# SCH-Unified_Sheet_2_Altium.net
KiCad netlist of a schematic drawn in Altium Designer
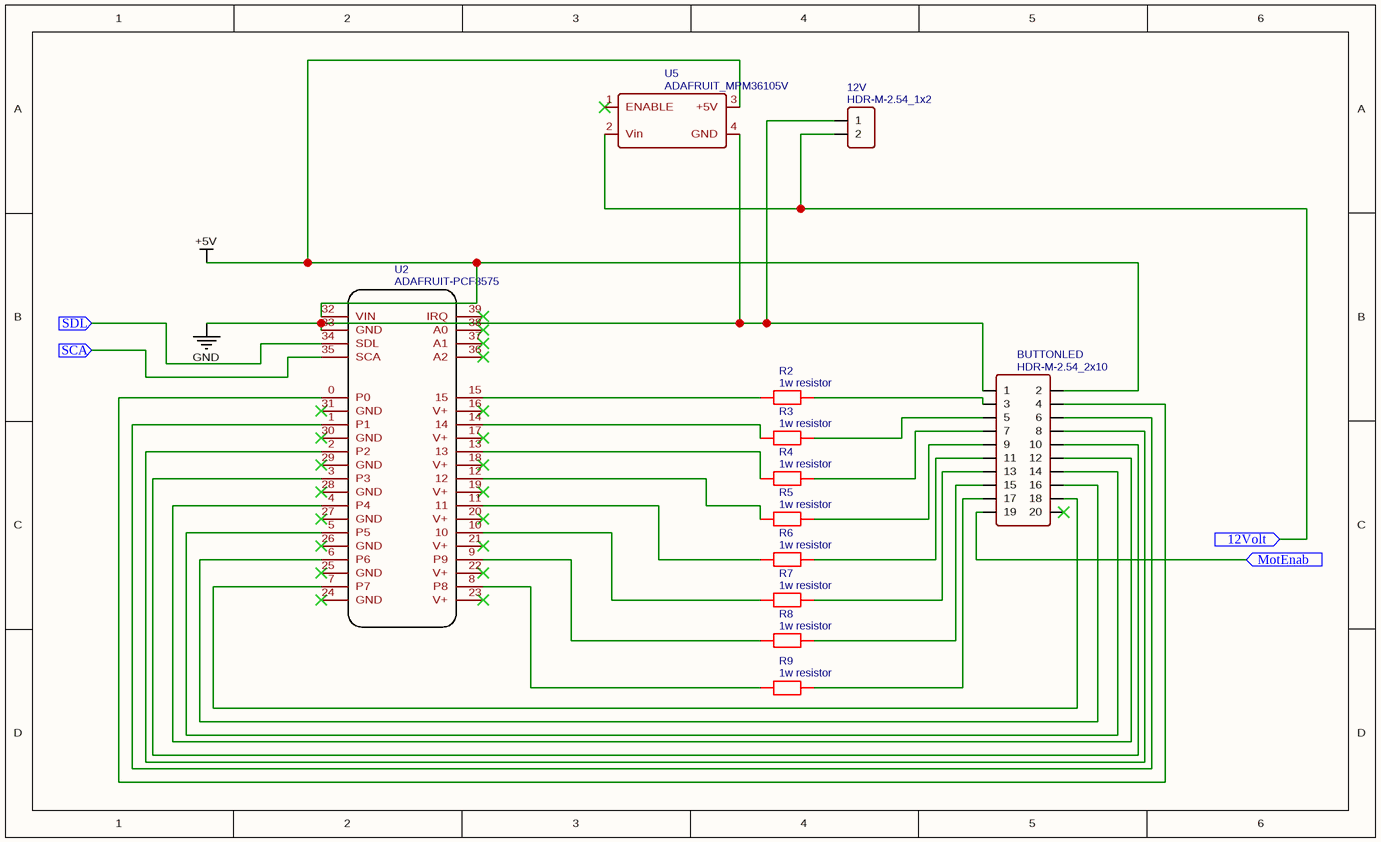
[diagram p0: SCH-Unified_Sheet_2_Altium.schdoc]

(export (version "E")
  (design (tool "Eeschema 10.0.6"))
  (components
    (comp (ref "12V")
      (value "HDR-M-2.54_1x2")
      (fields (field (name "CONTRIBUTOR") "LCEDA_Lib"))
      (libsource (lib "altium-import") (part "root_0_HDR-M-2.54_1x2_"))
    )
    (comp (ref "BUTTONLED")
      (value "HDR-M-2.54_2x10")
      (fields (field (name "CONTRIBUTOR") "LCEDA_Lib"))
      (libsource (lib "altium-import") (part "root_0_HDR-M-2.54_2x10_"))
    )
    (comp (ref "R2")
      (value "1w resistor")
      (fields (field (name "CONTRIBUTOR") "Kagutsuchi"))
      (libsource (lib "altium-import") (part "root_0_1w resistor_"))
    )
    (comp (ref "R3")
      (value "1w resistor")
      (fields (field (name "CONTRIBUTOR") "Kagutsuchi"))
      (libsource (lib "altium-import") (part "root_0_1w resistor_"))
    )
    (comp (ref "R4")
      (value "1w resistor")
      (fields (field (name "CONTRIBUTOR") "Kagutsuchi"))
      (libsource (lib "altium-import") (part "root_0_1w resistor_"))
    )
    (comp (ref "R5")
      (value "1w resistor")
      (fields (field (name "CONTRIBUTOR") "Kagutsuchi"))
      (libsource (lib "altium-import") (part "root_0_1w resistor_"))
    )
    (comp (ref "R6")
      (value "1w resistor")
      (fields (field (name "CONTRIBUTOR") "Kagutsuchi"))
      (libsource (lib "altium-import") (part "root_0_1w resistor_"))
    )
    (comp (ref "R7")
      (value "1w resistor")
      (fields (field (name "CONTRIBUTOR") "Kagutsuchi"))
      (libsource (lib "altium-import") (part "root_0_1w resistor_"))
    )
    (comp (ref "R8")
      (value "1w resistor")
      (fields (field (name "CONTRIBUTOR") "Kagutsuchi"))
      (libsource (lib "altium-import") (part "root_0_1w resistor_"))
    )
    (comp (ref "R9")
      (value "1w resistor")
      (fields (field (name "CONTRIBUTOR") "Kagutsuchi"))
      (libsource (lib "altium-import") (part "root_0_1w resistor_"))
    )
    (comp (ref "U2")
      (value "ADAFRUIT-PCF8575")
      (fields (field (name "CONTRIBUTOR") "williambaucom"))
      (libsource (lib "altium-import") (part "root_3_ADAFRUIT-PCF8575_"))
    )
    (comp (ref "U5")
      (value "ADAFRUIT_MPM36105V")
      (fields (field (name "CONTRIBUTOR") "Aidan Farley"))
      (libsource (lib "altium-import") (part "root_0_ADAFRUIT_MPM36105V_"))
    )
  )
  (nets
    (net (code "1") (name "+5V") (class "Default")
      (node (ref "BUTTONLED") (pin "2") (pinfunction "2_2") (pintype "passive"))
      (node (ref "U2") (pin "32") (pinfunction "VIN_32") (pintype "passive"))
      (node (ref "U5") (pin "3") (pinfunction "+5V_3") (pintype "passive"))
    )
    (net (code "2") (name "/12Volt") (class "Default")
      (node (ref "12V") (pin "2") (pinfunction "2_2") (pintype "passive"))
      (node (ref "U5") (pin "2") (pinfunction "Vin_2") (pintype "passive"))
    )
    (net (code "3") (name "/MotEnab") (class "Default")
      (node (ref "BUTTONLED") (pin "19") (pinfunction "19_19") (pintype "passive"))
    )
    (net (code "4") (name "/SCA") (class "Default")
      (node (ref "U2") (pin "35") (pinfunction "SCA_35") (pintype "passive"))
    )
    (net (code "5") (name "/SDL") (class "Default")
      (node (ref "U2") (pin "34") (pinfunction "SDL_34") (pintype "passive"))
    )
    (net (code "6") (name "GND") (class "Default")
      (node (ref "12V") (pin "1") (pinfunction "1_1") (pintype "passive"))
      (node (ref "BUTTONLED") (pin "1") (pinfunction "1_1") (pintype "passive"))
      (node (ref "U2") (pin "33") (pinfunction "GND_33") (pintype "passive"))
      (node (ref "U5") (pin "4") (pinfunction "GND_4") (pintype "passive"))
    )
    (net (code "7") (name "Net-(R2-1)") (class "Default")
      (node (ref "BUTTONLED") (pin "3") (pinfunction "3_3") (pintype "passive"))
      (node (ref "R2") (pin "2") (pinfunction "1_2") (pintype "passive"))
    )
    (net (code "8") (name "Net-(R2-2)") (class "Default")
      (node (ref "R2") (pin "1") (pinfunction "2_1") (pintype "passive"))
      (node (ref "U2") (pin "15") (pinfunction "15_15") (pintype "passive"))
    )
    (net (code "9") (name "Net-(R3-1)") (class "Default")
      (node (ref "BUTTONLED") (pin "5") (pinfunction "5_5") (pintype "passive"))
      (node (ref "R3") (pin "2") (pinfunction "1_2") (pintype "passive"))
    )
    (net (code "10") (name "Net-(R3-2)") (class "Default")
      (node (ref "R3") (pin "1") (pinfunction "2_1") (pintype "passive"))
      (node (ref "U2") (pin "14") (pinfunction "14_14") (pintype "passive"))
    )
    (net (code "11") (name "Net-(R4-1)") (class "Default")
      (node (ref "BUTTONLED") (pin "7") (pinfunction "7_7") (pintype "passive"))
      (node (ref "R4") (pin "2") (pinfunction "1_2") (pintype "passive"))
    )
    (net (code "12") (name "Net-(R4-2)") (class "Default")
      (node (ref "R4") (pin "1") (pinfunction "2_1") (pintype "passive"))
      (node (ref "U2") (pin "13") (pinfunction "13_13") (pintype "passive"))
    )
    (net (code "13") (name "Net-(R5-1)") (class "Default")
      (node (ref "BUTTONLED") (pin "9") (pinfunction "9_9") (pintype "passive"))
      (node (ref "R5") (pin "2") (pinfunction "1_2") (pintype "passive"))
    )
    (net (code "14") (name "Net-(R5-2)") (class "Default")
      (node (ref "R5") (pin "1") (pinfunction "2_1") (pintype "passive"))
      (node (ref "U2") (pin "12") (pinfunction "12_12") (pintype "passive"))
    )
    (net (code "15") (name "Net-(R6-1)") (class "Default")
      (node (ref "BUTTONLED") (pin "11") (pinfunction "11_11") (pintype "passive"))
      (node (ref "R6") (pin "2") (pinfunction "1_2") (pintype "passive"))
    )
    (net (code "16") (name "Net-(R6-2)") (class "Default")
      (node (ref "R6") (pin "1") (pinfunction "2_1") (pintype "passive"))
      (node (ref "U2") (pin "11") (pinfunction "11_11") (pintype "passive"))
    )
    (net (code "17") (name "Net-(R7-1)") (class "Default")
      (node (ref "BUTTONLED") (pin "13") (pinfunction "13_13") (pintype "passive"))
      (node (ref "R7") (pin "2") (pinfunction "1_2") (pintype "passive"))
    )
    (net (code "18") (name "Net-(R7-2)") (class "Default")
      (node (ref "R7") (pin "1") (pinfunction "2_1") (pintype "passive"))
      (node (ref "U2") (pin "10") (pinfunction "10_10") (pintype "passive"))
    )
    (net (code "19") (name "Net-(R8-1)") (class "Default")
      (node (ref "BUTTONLED") (pin "15") (pinfunction "15_15") (pintype "passive"))
      (node (ref "R8") (pin "2") (pinfunction "1_2") (pintype "passive"))
    )
    (net (code "20") (name "Net-(R8-2)") (class "Default")
      (node (ref "R8") (pin "1") (pinfunction "2_1") (pintype "passive"))
      (node (ref "U2") (pin "9") (pinfunction "P9_9") (pintype "passive"))
    )
    (net (code "21") (name "Net-(R9-1)") (class "Default")
      (node (ref "BUTTONLED") (pin "17") (pinfunction "17_17") (pintype "passive"))
      (node (ref "R9") (pin "2") (pinfunction "1_2") (pintype "passive"))
    )
    (net (code "22") (name "Net-(R9-2)") (class "Default")
      (node (ref "R9") (pin "1") (pinfunction "2_1") (pintype "passive"))
      (node (ref "U2") (pin "8") (pinfunction "P8_8") (pintype "passive"))
    )
    (net (code "23") (name "Net-(U2-P0)") (class "Default")
      (node (ref "BUTTONLED") (pin "4") (pinfunction "4_4") (pintype "passive"))
      (node (ref "U2") (pin "0") (pinfunction "P0_0") (pintype "passive"))
    )
    (net (code "24") (name "Net-(U2-P1)") (class "Default")
      (node (ref "BUTTONLED") (pin "6") (pinfunction "6_6") (pintype "passive"))
      (node (ref "U2") (pin "1") (pinfunction "P1_1") (pintype "passive"))
    )
    (net (code "25") (name "Net-(U2-P2)") (class "Default")
      (node (ref "BUTTONLED") (pin "8") (pinfunction "8_8") (pintype "passive"))
      (node (ref "U2") (pin "2") (pinfunction "P2_2") (pintype "passive"))
    )
    (net (code "26") (name "Net-(U2-P3)") (class "Default")
      (node (ref "BUTTONLED") (pin "10") (pinfunction "10_10") (pintype "passive"))
      (node (ref "U2") (pin "3") (pinfunction "P3_3") (pintype "passive"))
    )
    (net (code "27") (name "Net-(U2-P4)") (class "Default")
      (node (ref "BUTTONLED") (pin "12") (pinfunction "12_12") (pintype "passive"))
      (node (ref "U2") (pin "4") (pinfunction "P4_4") (pintype "passive"))
    )
    (net (code "28") (name "Net-(U2-P5)") (class "Default")
      (node (ref "BUTTONLED") (pin "14") (pinfunction "14_14") (pintype "passive"))
      (node (ref "U2") (pin "5") (pinfunction "P5_5") (pintype "passive"))
    )
    (net (code "29") (name "Net-(U2-P6)") (class "Default")
      (node (ref "BUTTONLED") (pin "16") (pinfunction "16_16") (pintype "passive"))
      (node (ref "U2") (pin "6") (pinfunction "P6_6") (pintype "passive"))
    )
    (net (code "30") (name "Net-(U2-P7)") (class "Default")
      (node (ref "BUTTONLED") (pin "18") (pinfunction "18_18") (pintype "passive"))
      (node (ref "U2") (pin "7") (pinfunction "P7_7") (pintype "passive"))
    )
    (net (code "31") (name "unconnected-(BUTTONLED-Pad20)") (class "Default")
      (node (ref "BUTTONLED") (pin "20") (pinfunction "20_20") (pintype "passive+no_connect"))
    )
    (net (code "32") (name "unconnected-(U2-A0-Pad38)") (class "Default")
      (node (ref "U2") (pin "38") (pinfunction "A0_38") (pintype "passive+no_connect"))
    )
    (net (code "33") (name "unconnected-(U2-A1-Pad37)") (class "Default")
      (node (ref "U2") (pin "37") (pinfunction "A1_37") (pintype "passive+no_connect"))
    )
    (net (code "34") (name "unconnected-(U2-A2-Pad36)") (class "Default")
      (node (ref "U2") (pin "36") (pinfunction "A2_36") (pintype "passive+no_connect"))
    )
    (net (code "35") (name "unconnected-(U2-GND-Pad24)") (class "Default")
      (node (ref "U2") (pin "24") (pinfunction "GND_24") (pintype "passive+no_connect"))
    )
    (net (code "36") (name "unconnected-(U2-GND-Pad25)") (class "Default")
      (node (ref "U2") (pin "25") (pinfunction "GND_25") (pintype "passive+no_connect"))
    )
    (net (code "37") (name "unconnected-(U2-GND-Pad26)") (class "Default")
      (node (ref "U2") (pin "26") (pinfunction "GND_26") (pintype "passive+no_connect"))
    )
    (net (code "38") (name "unconnected-(U2-GND-Pad27)") (class "Default")
      (node (ref "U2") (pin "27") (pinfunction "GND_27") (pintype "passive+no_connect"))
    )
    (net (code "39") (name "unconnected-(U2-GND-Pad28)") (class "Default")
      (node (ref "U2") (pin "28") (pinfunction "GND_28") (pintype "passive+no_connect"))
    )
    (net (code "40") (name "unconnected-(U2-GND-Pad29)") (class "Default")
      (node (ref "U2") (pin "29") (pinfunction "GND_29") (pintype "passive+no_connect"))
    )
    (net (code "41") (name "unconnected-(U2-GND-Pad30)") (class "Default")
      (node (ref "U2") (pin "30") (pinfunction "GND_30") (pintype "passive+no_connect"))
    )
    (net (code "42") (name "unconnected-(U2-GND-Pad31)") (class "Default")
      (node (ref "U2") (pin "31") (pinfunction "GND_31") (pintype "passive+no_connect"))
    )
    (net (code "43") (name "unconnected-(U2-IRQ-Pad39)") (class "Default")
      (node (ref "U2") (pin "39") (pinfunction "IRQ_39") (pintype "passive+no_connect"))
    )
    (net (code "44") (name "unconnected-(U2-V+-Pad16)") (class "Default")
      (node (ref "U2") (pin "16") (pinfunction "V+_16") (pintype "passive+no_connect"))
    )
    (net (code "45") (name "unconnected-(U2-V+-Pad17)") (class "Default")
      (node (ref "U2") (pin "17") (pinfunction "V+_17") (pintype "passive+no_connect"))
    )
    (net (code "46") (name "unconnected-(U2-V+-Pad18)") (class "Default")
      (node (ref "U2") (pin "18") (pinfunction "V+_18") (pintype "passive+no_connect"))
    )
    (net (code "47") (name "unconnected-(U2-V+-Pad19)") (class "Default")
      (node (ref "U2") (pin "19") (pinfunction "V+_19") (pintype "passive+no_connect"))
    )
    (net (code "48") (name "unconnected-(U2-V+-Pad20)") (class "Default")
      (node (ref "U2") (pin "20") (pinfunction "V+_20") (pintype "passive+no_connect"))
    )
    (net (code "49") (name "unconnected-(U2-V+-Pad21)") (class "Default")
      (node (ref "U2") (pin "21") (pinfunction "V+_21") (pintype "passive+no_connect"))
    )
    (net (code "50") (name "unconnected-(U2-V+-Pad22)") (class "Default")
      (node (ref "U2") (pin "22") (pinfunction "V+_22") (pintype "passive+no_connect"))
    )
    (net (code "51") (name "unconnected-(U2-V+-Pad23)") (class "Default")
      (node (ref "U2") (pin "23") (pinfunction "V+_23") (pintype "passive+no_connect"))
    )
    (net (code "52") (name "unconnected-(U5-ENABLE-Pad1)") (class "Default")
      (node (ref "U5") (pin "1") (pinfunction "ENABLE_1") (pintype "passive+no_connect"))
    )
  )
)
